# 5V-and-3V3-ldo.net
KiCad netlist of a schematic drawn in Altium Designer
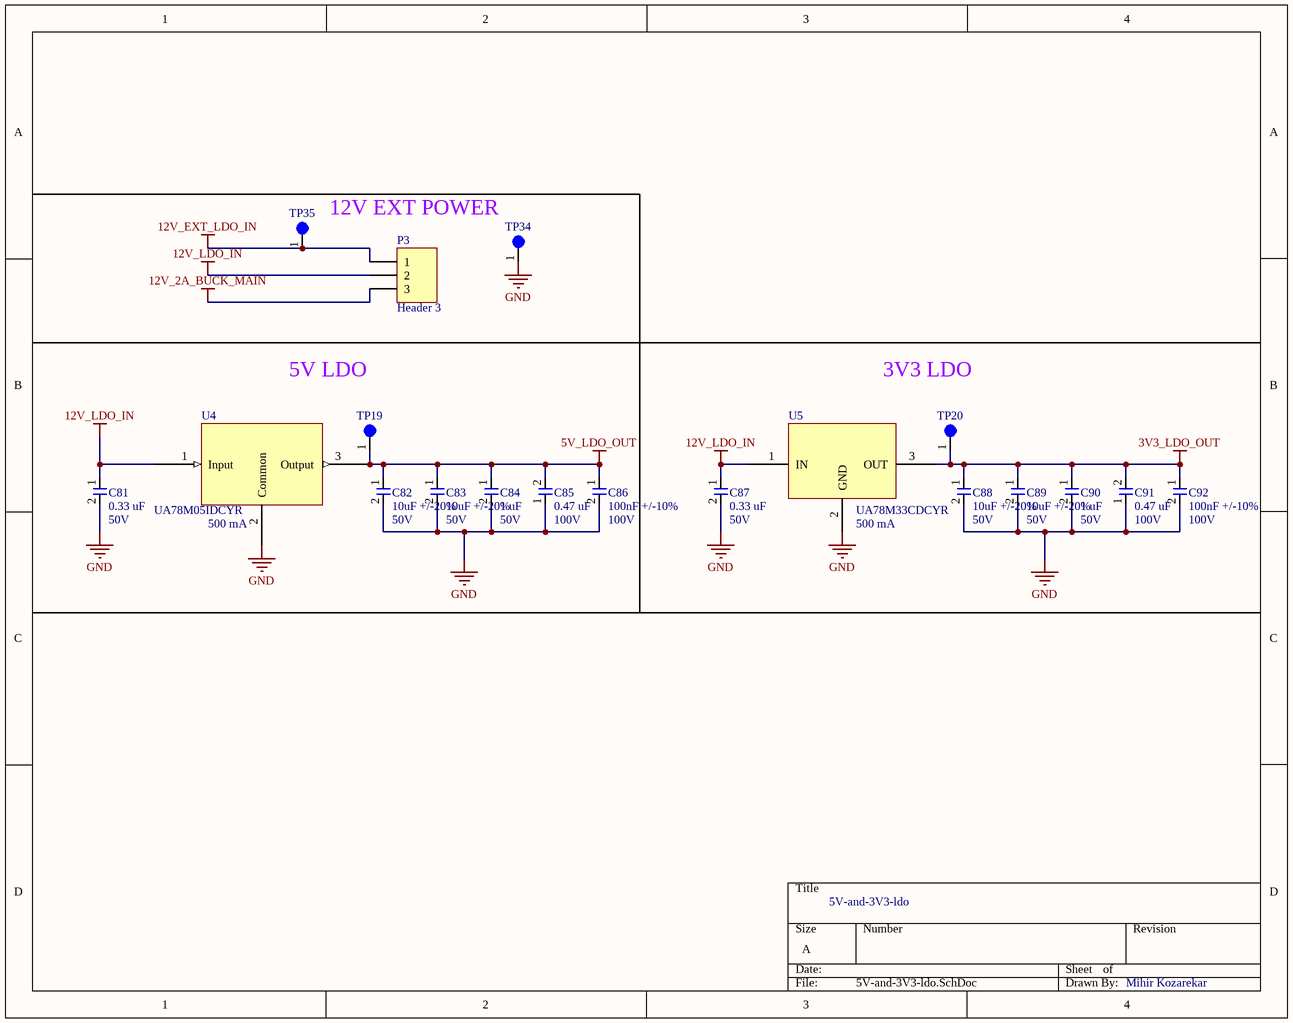
[diagram p0: 5V-and-3V3-ldo.SchDoc]

(export (version "E")
  (design (tool "Eeschema 10.0.6"))
  (components
    (comp (ref "C81")
      (value "CGA3E3X7R1H334K080AB")
      (footprint "CAP-0603")
      (description "0.33 µF ±10% 50V Ceramic Capacitor X7R 0603 (1608 Metric)")
      (fields
        (field (name "MANUFACTURER") "TDK Corporation")
        (field (name "TOLERANCE") "+/- 10%")
        (field (name "CAPACITANCE") "0.33 uF")
        (field (name "VOLTAGE") "50V")
      )
      (libsource (lib "MasterLib") (part "CAP-0.33uF-0001"))
    )
    (comp (ref "C82")
      (value "CL31B106KBHNNNE")
      (footprint "CAP-1206")
      (description "10 µF ±10% 50V Ceramic Capacitor X7R 1206 (3216 Metric)")
      (fields
        (field (name "MANUFACTURER") "Samsung Electro-Mechanics")
        (field (name "CAPACITANCE") "10uF +/-20%")
        (field (name "VOLTAGE RATING") "50V")
      )
      (libsource (lib "MasterLib") (part "CAP-10U-0001"))
    )
    (comp (ref "C83")
      (value "CL31B106KBHNNNE")
      (footprint "CAP-1206")
      (description "10 µF ±10% 50V Ceramic Capacitor X7R 1206 (3216 Metric)")
      (fields
        (field (name "MANUFACTURER") "Samsung Electro-Mechanics")
        (field (name "CAPACITANCE") "10uF +/-20%")
        (field (name "VOLTAGE RATING") "50V")
      )
      (libsource (lib "MasterLib") (part "CAP-10U-0001"))
    )
    (comp (ref "C84")
      (value "UMK107AB7105KA-T")
      (footprint "CAP-0603")
      (description "1 µF ±10% 50V Ceramic Capacitor X7R 0603 (1608 Metric)")
      (fields (field (name "CAPACITANCE") "1 uF") (field (name "VOLTAGE") "50V"))
      (libsource (lib "MasterLib") (part "CAP-1U-0002"))
    )
    (comp (ref "C85")
      (value "KAM21KR72A474KL")
      (footprint "CAP-0805")
      (description "0.47 µF ±10% 100V Ceramic Capacitor X7R 0805 (2012 Metric)")
      (fields
        (field (name "TOLERANCE") "+/- 10%")
        (field (name "CAPACITANCE") "0.47 uF")
        (field (name "VOLTAGE") "100V")
      )
      (libsource (lib "MasterLib") (part "CAP-0.47U-0001"))
    )
    (comp (ref "C86")
      (value "CC0603KRX7R0BB104")
      (footprint "CAP-0603")
      (description "CAP CER 0.1UF 100V X7R 0603")
      (fields
        (field (name "MANUFACTURER") "YAGEO")
        (field (name "CAPACITANCE") "100nF +/-10%")
        (field (name "VOLTAGE RATING") "100V")
      )
      (libsource (lib "MasterLib") (part "CAP-100N-0001"))
    )
    (comp (ref "C87")
      (value "CGA3E3X7R1H334K080AB")
      (footprint "CAP-0603")
      (description "0.33 µF ±10% 50V Ceramic Capacitor X7R 0603 (1608 Metric)")
      (fields
        (field (name "MANUFACTURER") "TDK Corporation")
        (field (name "TOLERANCE") "+/- 10%")
        (field (name "CAPACITANCE") "0.33 uF")
        (field (name "VOLTAGE") "50V")
      )
      (libsource (lib "MasterLib") (part "CAP-0.33uF-0001"))
    )
    (comp (ref "C88")
      (value "CL31B106KBHNNNE")
      (footprint "CAP-1206")
      (description "10 µF ±10% 50V Ceramic Capacitor X7R 1206 (3216 Metric)")
      (fields
        (field (name "MANUFACTURER") "Samsung Electro-Mechanics")
        (field (name "CAPACITANCE") "10uF +/-20%")
        (field (name "VOLTAGE RATING") "50V")
      )
      (libsource (lib "MasterLib") (part "CAP-10U-0001"))
    )
    (comp (ref "C89")
      (value "CL31B106KBHNNNE")
      (footprint "CAP-1206")
      (description "10 µF ±10% 50V Ceramic Capacitor X7R 1206 (3216 Metric)")
      (fields
        (field (name "MANUFACTURER") "Samsung Electro-Mechanics")
        (field (name "CAPACITANCE") "10uF +/-20%")
        (field (name "VOLTAGE RATING") "50V")
      )
      (libsource (lib "MasterLib") (part "CAP-10U-0001"))
    )
    (comp (ref "C90")
      (value "UMK107AB7105KA-T")
      (footprint "CAP-0603")
      (description "1 µF ±10% 50V Ceramic Capacitor X7R 0603 (1608 Metric)")
      (fields (field (name "CAPACITANCE") "1 uF") (field (name "VOLTAGE") "50V"))
      (libsource (lib "MasterLib") (part "CAP-1U-0002"))
    )
    (comp (ref "C91")
      (value "KAM21KR72A474KL")
      (footprint "CAP-0805")
      (description "0.47 µF ±10% 100V Ceramic Capacitor X7R 0805 (2012 Metric)")
      (fields
        (field (name "TOLERANCE") "+/- 10%")
        (field (name "CAPACITANCE") "0.47 uF")
        (field (name "VOLTAGE") "100V")
      )
      (libsource (lib "MasterLib") (part "CAP-0.47U-0001"))
    )
    (comp (ref "C92")
      (value "CC0603KRX7R0BB104")
      (footprint "CAP-0603")
      (description "CAP CER 0.1UF 100V X7R 0603")
      (fields
        (field (name "MANUFACTURER") "YAGEO")
        (field (name "CAPACITANCE") "100nF +/-10%")
        (field (name "VOLTAGE RATING") "100V")
      )
      (libsource (lib "MasterLib") (part "CAP-100N-0001"))
    )
    (comp (ref "P3")
      (value "Header 3")
      (footprint "HDR1X3")
      (description "Header, 3-Pin")
      (fields (field (name "PUBLISHER") "Altium Limited"))
      (libsource (lib "Miscellaneous Connectors") (part "Header 3"))
    )
    (comp (ref "TP19")
      (value "5003")
      (footprint "TEST-POINT-0001")
      (description "Oranange PC Test Point, Miniature Phoisphor Bronze Silver Plating Through Hole Mounting Type")
      (libsource (lib "MasterLib") (part "TEST-POINT-0001"))
    )
    (comp (ref "TP20")
      (value "5003")
      (footprint "TEST-POINT-0001")
      (description "Oranange PC Test Point, Miniature Phoisphor Bronze Silver Plating Through Hole Mounting Type")
      (libsource (lib "MasterLib") (part "TEST-POINT-0001"))
    )
    (comp (ref "TP34")
      (value "5003")
      (footprint "TEST-POINT-0001")
      (description "Oranange PC Test Point, Miniature Phoisphor Bronze Silver Plating Through Hole Mounting Type")
      (libsource (lib "MasterLib") (part "TEST-POINT-0001"))
    )
    (comp (ref "TP35")
      (value "5003")
      (footprint "TEST-POINT-0001")
      (description "Oranange PC Test Point, Miniature Phoisphor Bronze Silver Plating Through Hole Mounting Type")
      (libsource (lib "MasterLib") (part "TEST-POINT-0001"))
    )
    (comp (ref "U4")
      (value "UA78M05IDCYR")
      (footprint "IC-SOT-223-4")
      (description "Linear Voltage Regulator IC Positive Fixed 1 Output 500mA SOT-223-4")
      (fields (field (name "MANUFACTURER") "Texas Instruments") (field (name "CURRENT") "500 mA"))
      (libsource (lib "MasterLib") (part "IC-LDO-5V-0003"))
    )
    (comp (ref "U5")
      (value "UA78M33CDCYR")
      (footprint "IC-SOT-223-4")
      (description "Linear Voltage Regulator IC Positive Fixed 1 Output 500mA SOT-223-4")
      (fields (field (name "CURRENT") "500 mA"))
      (libsource (lib "MasterLib") (part "IC-LDO-3.3V-0002"))
    )
  )
  (nets
    (net (code "1") (name "3V3_LDO_OUT") (class "Default")
      (node (ref "C88") (pin "1") (pinfunction "1_1") (pintype "passive"))
      (node (ref "C89") (pin "1") (pinfunction "1_1") (pintype "passive"))
      (node (ref "C90") (pin "1") (pinfunction "1_1") (pintype "passive"))
      (node (ref "C91") (pin "2") (pinfunction "2_2") (pintype "passive"))
      (node (ref "C92") (pin "1") (pinfunction "1_1") (pintype "passive"))
      (node (ref "TP20") (pin "1") (pinfunction "0_1") (pintype "passive"))
      (node (ref "U5") (pin "3") (pinfunction "OUT_3") (pintype "power_in"))
    )
    (net (code "2") (name "5V_LDO_OUT") (class "Default")
      (node (ref "C82") (pin "1") (pinfunction "1_1") (pintype "passive"))
      (node (ref "C83") (pin "1") (pinfunction "1_1") (pintype "passive"))
      (node (ref "C84") (pin "1") (pinfunction "1_1") (pintype "passive"))
      (node (ref "C85") (pin "2") (pinfunction "2_2") (pintype "passive"))
      (node (ref "C86") (pin "1") (pinfunction "1_1") (pintype "passive"))
      (node (ref "TP19") (pin "1") (pinfunction "0_1") (pintype "passive"))
      (node (ref "U4") (pin "3") (pinfunction "Output_3") (pintype "output"))
    )
    (net (code "3") (name "12V_2A_BUCK_MAIN") (class "Default")
      (node (ref "P3") (pin "3") (pinfunction "3_3") (pintype "passive"))
    )
    (net (code "4") (name "12V_EXT_LDO_IN") (class "Default")
      (node (ref "P3") (pin "1") (pinfunction "1_1") (pintype "passive"))
      (node (ref "TP35") (pin "1") (pinfunction "0_1") (pintype "passive"))
    )
    (net (code "5") (name "12V_LDO_IN") (class "Default")
      (node (ref "C81") (pin "1") (pinfunction "1_1") (pintype "passive"))
      (node (ref "C87") (pin "1") (pinfunction "1_1") (pintype "passive"))
      (node (ref "P3") (pin "2") (pinfunction "2_2") (pintype "passive"))
      (node (ref "U4") (pin "1") (pinfunction "Input_1") (pintype "input"))
      (node (ref "U5") (pin "1") (pinfunction "IN_1") (pintype "power_in"))
    )
    (net (code "6") (name "GND") (class "Default")
      (node (ref "C81") (pin "2") (pinfunction "2_2") (pintype "passive"))
      (node (ref "C82") (pin "2") (pinfunction "2_2") (pintype "passive"))
      (node (ref "C83") (pin "2") (pinfunction "2_2") (pintype "passive"))
      (node (ref "C84") (pin "2") (pinfunction "2_2") (pintype "passive"))
      (node (ref "C85") (pin "1") (pinfunction "1_1") (pintype "passive"))
      (node (ref "C86") (pin "2") (pinfunction "2_2") (pintype "passive"))
      (node (ref "C87") (pin "2") (pinfunction "2_2") (pintype "passive"))
      (node (ref "C88") (pin "2") (pinfunction "2_2") (pintype "passive"))
      (node (ref "C89") (pin "2") (pinfunction "2_2") (pintype "passive"))
      (node (ref "C90") (pin "2") (pinfunction "2_2") (pintype "passive"))
      (node (ref "C91") (pin "1") (pinfunction "1_1") (pintype "passive"))
      (node (ref "C92") (pin "2") (pinfunction "2_2") (pintype "passive"))
      (node (ref "TP34") (pin "1") (pinfunction "0_1") (pintype "passive"))
      (node (ref "U4") (pin "2") (pinfunction "Common_2") (pintype "power_in"))
      (node (ref "U5") (pin "2") (pinfunction "GND_2") (pintype "power_in"))
    )
  )
)
